# tgs2611-c00-v3.net
KiCad netlist of a schematic drawn in EAGLE
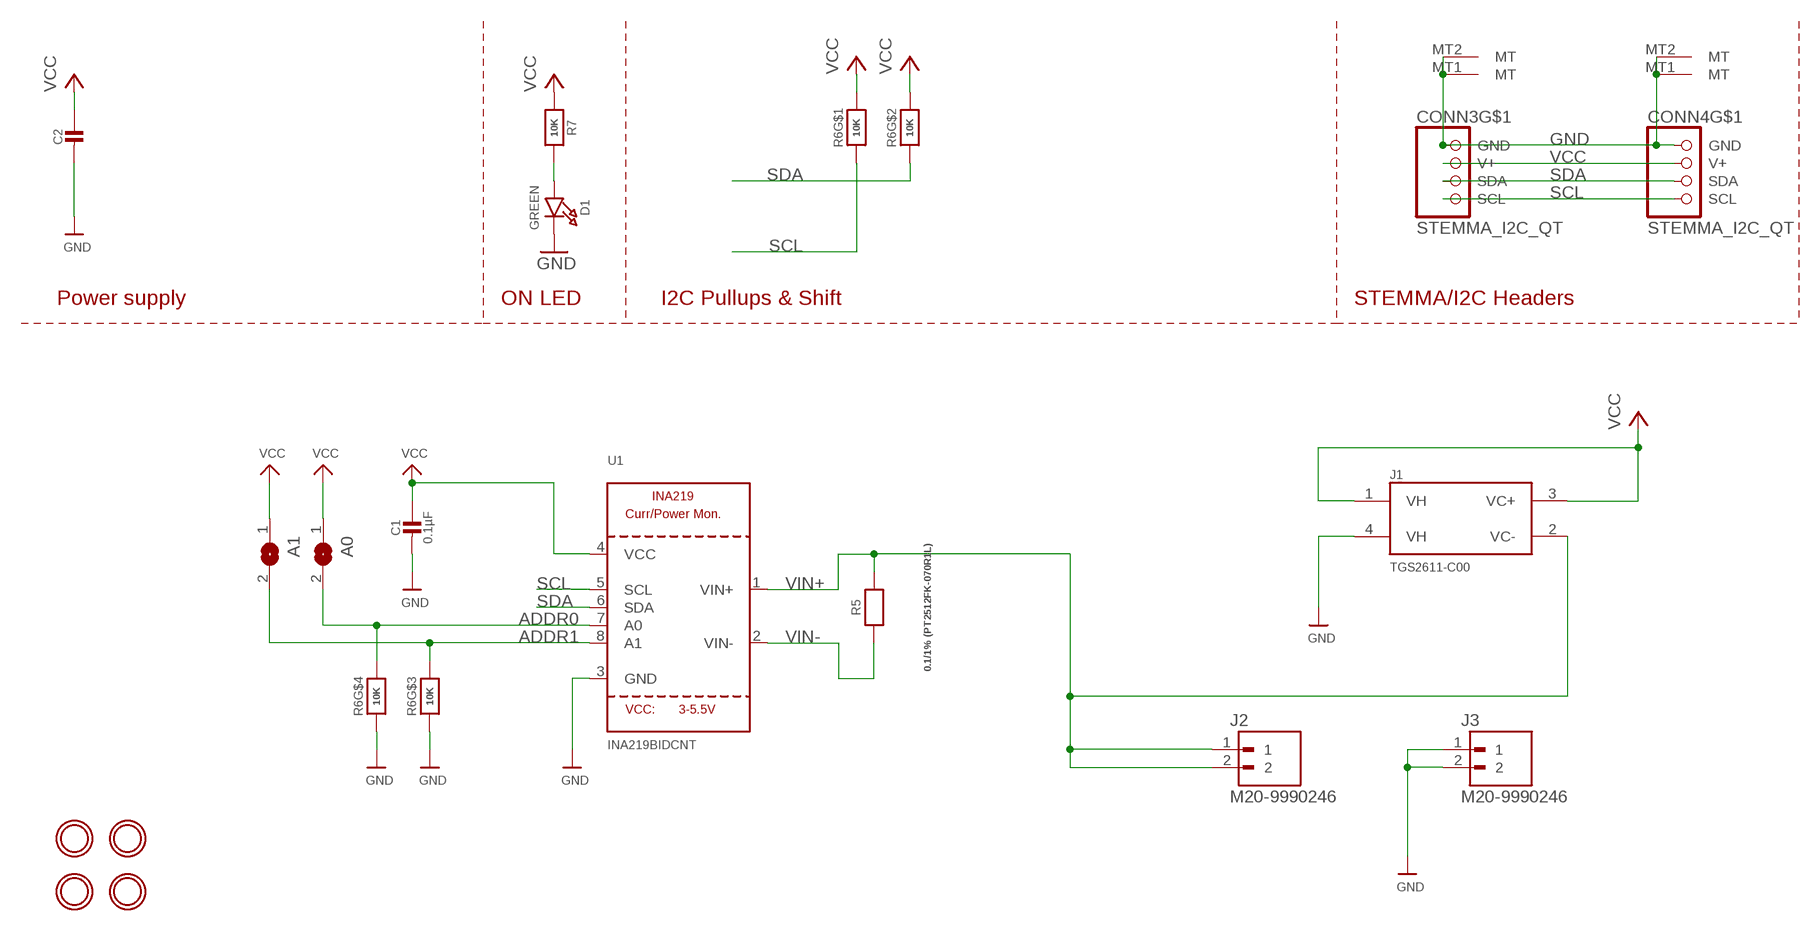
[diagram p0: schematic, sheet 1]

(export (version "E")
  (design (tool "Eeschema 10.0.6"))
  (components
    (comp (ref "A0")
      (value "SOLDERJUMPERREFLOW_NOPASTE")
      (footprint "eagle-import:SOLDERJUMPER_REFLOW_NOPASTE")
      (libsource (lib "eagle-import") (part "SOLDERJUMPERREFLOW_NOPASTE"))
    )
    (comp (ref "A1")
      (value "SOLDERJUMPERREFLOW_NOPASTE")
      (footprint "eagle-import:SOLDERJUMPER_REFLOW_NOPASTE")
      (libsource (lib "eagle-import") (part "SOLDERJUMPERREFLOW_NOPASTE"))
    )
    (comp (ref "C1")
      (value "0.1µF")
      (footprint "eagle-import:0603-NO")
      (libsource (lib "eagle-import") (part "CAP_CERAMIC0603_NO"))
    )
    (comp (ref "C2")
      (value "10uF")
      (footprint "eagle-import:0805-NO")
      (libsource (lib "eagle-import") (part "CAP_CERAMIC0805-NOOUTLINE"))
    )
    (comp (ref "CONN3")
      (value "STEMMA_I2C_QT")
      (footprint "eagle-import:JST_SH4")
      (libsource (lib "eagle-import") (part "STEMMA_I2C_QT"))
    )
    (comp (ref "CONN4")
      (value "STEMMA_I2C_QT")
      (footprint "eagle-import:JST_SH4")
      (libsource (lib "eagle-import") (part "STEMMA_I2C_QT"))
    )
    (comp (ref "D1")
      (value "GREEN")
      (footprint "eagle-import:CHIPLED_0603_NOOUTLINE")
      (libsource (lib "eagle-import") (part "LED0603_NOOUTLINE"))
    )
    (comp (ref "J1")
      (value "TGS2611-C00")
      (footprint "eagle-import:TO180P920X780-4P")
      (fields (field (name "MF") "Figaro"))
      (libsource (lib "eagle-import") (part "TGS2611-C00"))
    )
    (comp (ref "J2")
      (value "M20-9990246")
      (footprint "eagle-import:HARWIN_M20-9990246")
      (fields (field (name "MANUFACTURER") "Harwin"))
      (libsource (lib "eagle-import") (part "M20-9990246"))
    )
    (comp (ref "J3")
      (value "M20-9990246")
      (footprint "eagle-import:HARWIN_M20-9990246")
      (fields (field (name "MANUFACTURER") "Harwin"))
      (libsource (lib "eagle-import") (part "M20-9990246"))
    )
    (comp (ref "R5")
      (value "0.1/1% (PT2512FK-070R1L)")
      (footprint "eagle-import:2512")
      (libsource (lib "eagle-import") (part "RESISTOR2512"))
    )
    (comp (ref "R6")
      (value "10K")
      (footprint "eagle-import:RESPACK_4X0603")
      (libsource (lib "eagle-import") (part "RESISTOR_4PACK"))
    )
    (comp (ref "R7")
      (value "10K")
      (footprint "eagle-import:0603-NO")
      (libsource (lib "eagle-import") (part "RESISTOR_0603_NOOUT"))
    )
    (comp (ref "U$20")
      (value "MOUNTINGHOLE2.5")
      (footprint "eagle-import:MOUNTINGHOLE_2.5_PLATED")
      (libsource (lib "eagle-import") (part "MOUNTINGHOLE2.5"))
    )
    (comp (ref "U$21")
      (value "MOUNTINGHOLE2.5")
      (footprint "eagle-import:MOUNTINGHOLE_2.5_PLATED")
      (libsource (lib "eagle-import") (part "MOUNTINGHOLE2.5"))
    )
    (comp (ref "U$25")
      (value "MOUNTINGHOLE2.5")
      (footprint "eagle-import:MOUNTINGHOLE_2.5_PLATED")
      (libsource (lib "eagle-import") (part "MOUNTINGHOLE2.5"))
    )
    (comp (ref "U$27")
      (value "MOUNTINGHOLE2.5")
      (footprint "eagle-import:MOUNTINGHOLE_2.5_PLATED")
      (libsource (lib "eagle-import") (part "MOUNTINGHOLE2.5"))
    )
    (comp (ref "U1")
      (value "INA219BIDCNT")
      (footprint "eagle-import:SOT23-8")
      (libsource (lib "eagle-import") (part "INA219"))
    )
  )
  (nets
    (net (code "1") (name "/ADDR0") (class "Default")
      (node (ref "A0") (pin "2") (pinfunction "2_2") (pintype "passive"))
      (node (ref "R6") (pin "5") (pinfunction "2_5") (pintype "passive"))
      (node (ref "U1") (pin "7") (pinfunction "A0_7") (pintype "bidirectional"))
    )
    (net (code "2") (name "/ADDR1") (class "Default")
      (node (ref "A1") (pin "2") (pinfunction "2_2") (pintype "passive"))
      (node (ref "R6") (pin "6") (pinfunction "2_6") (pintype "passive"))
      (node (ref "U1") (pin "8") (pinfunction "A1_8") (pintype "bidirectional"))
    )
    (net (code "3") (name "/SCL") (class "Default")
      (node (ref "CONN3") (pin "4") (pinfunction "SCL_4") (pintype "passive"))
      (node (ref "CONN4") (pin "4") (pinfunction "SCL_4") (pintype "passive"))
      (node (ref "R6") (pin "1") (pinfunction "1_1") (pintype "passive"))
      (node (ref "U1") (pin "5") (pinfunction "SCL_5") (pintype "bidirectional"))
    )
    (net (code "4") (name "/SDA") (class "Default")
      (node (ref "CONN3") (pin "3") (pinfunction "SDA_3") (pintype "passive"))
      (node (ref "CONN4") (pin "3") (pinfunction "SDA_3") (pintype "passive"))
      (node (ref "R6") (pin "2") (pinfunction "1_2") (pintype "passive"))
      (node (ref "U1") (pin "6") (pinfunction "SDA_6") (pintype "bidirectional"))
    )
    (net (code "5") (name "/VIN+") (class "Default")
      (node (ref "J1") (pin "2") (pinfunction "VC-_2") (pintype "power_in"))
      (node (ref "J2") (pin "1") (pinfunction "1_1") (pintype "passive"))
      (node (ref "J2") (pin "2") (pinfunction "2_2") (pintype "passive"))
      (node (ref "R5") (pin "2") (pinfunction "2_2") (pintype "passive"))
      (node (ref "U1") (pin "1") (pinfunction "VIN+_1") (pintype "bidirectional"))
    )
    (net (code "6") (name "/VIN-") (class "Default")
      (node (ref "R5") (pin "1") (pinfunction "1_1") (pintype "passive"))
      (node (ref "U1") (pin "2") (pinfunction "VIN-_2") (pintype "bidirectional"))
    )
    (net (code "7") (name "GND") (class "Default")
      (node (ref "C1") (pin "2") (pinfunction "2_2") (pintype "passive"))
      (node (ref "C2") (pin "2") (pinfunction "2_2") (pintype "passive"))
      (node (ref "CONN3") (pin "1") (pinfunction "GND_1") (pintype "passive"))
      (node (ref "CONN3") (pin "MT1") (pinfunction "MT_MT1") (pintype "bidirectional"))
      (node (ref "CONN3") (pin "MT2") (pinfunction "MT_MT2") (pintype "bidirectional"))
      (node (ref "CONN4") (pin "1") (pinfunction "GND_1") (pintype "passive"))
      (node (ref "CONN4") (pin "MT1") (pinfunction "MT_MT1") (pintype "bidirectional"))
      (node (ref "CONN4") (pin "MT2") (pinfunction "MT_MT2") (pintype "bidirectional"))
      (node (ref "D1") (pin "C") (pinfunction "C_C") (pintype "passive"))
      (node (ref "J1") (pin "4") (pinfunction "VH_4") (pintype "input"))
      (node (ref "J3") (pin "1") (pinfunction "1_1") (pintype "passive"))
      (node (ref "J3") (pin "2") (pinfunction "2_2") (pintype "passive"))
      (node (ref "R6") (pin "3") (pinfunction "1_3") (pintype "passive"))
      (node (ref "R6") (pin "4") (pinfunction "1_4") (pintype "passive"))
      (node (ref "U1") (pin "3") (pinfunction "GND_3") (pintype "power_in"))
    )
    (net (code "8") (name "Net-(D1-PadA)") (class "Default")
      (node (ref "D1") (pin "A") (pinfunction "A_A") (pintype "passive"))
      (node (ref "R7") (pin "2") (pinfunction "2_2") (pintype "passive"))
    )
    (net (code "9") (name "VCC") (class "Default")
      (node (ref "A0") (pin "1") (pinfunction "1_1") (pintype "passive"))
      (node (ref "A1") (pin "1") (pinfunction "1_1") (pintype "passive"))
      (node (ref "C1") (pin "1") (pinfunction "1_1") (pintype "passive"))
      (node (ref "C2") (pin "1") (pinfunction "1_1") (pintype "passive"))
      (node (ref "CONN3") (pin "2") (pinfunction "V+_2") (pintype "passive"))
      (node (ref "CONN4") (pin "2") (pinfunction "V+_2") (pintype "passive"))
      (node (ref "J1") (pin "1") (pinfunction "VH_1") (pintype "input"))
      (node (ref "J1") (pin "3") (pinfunction "VC+_3") (pintype "power_in"))
      (node (ref "R6") (pin "7") (pinfunction "2_7") (pintype "passive"))
      (node (ref "R6") (pin "8") (pinfunction "2_8") (pintype "passive"))
      (node (ref "R7") (pin "1") (pinfunction "1_1") (pintype "passive"))
      (node (ref "U1") (pin "4") (pinfunction "VCC_4") (pintype "power_in"))
    )
  )
)
